# ECG.net
KiCad netlist of a schematic drawn in Altium Designer
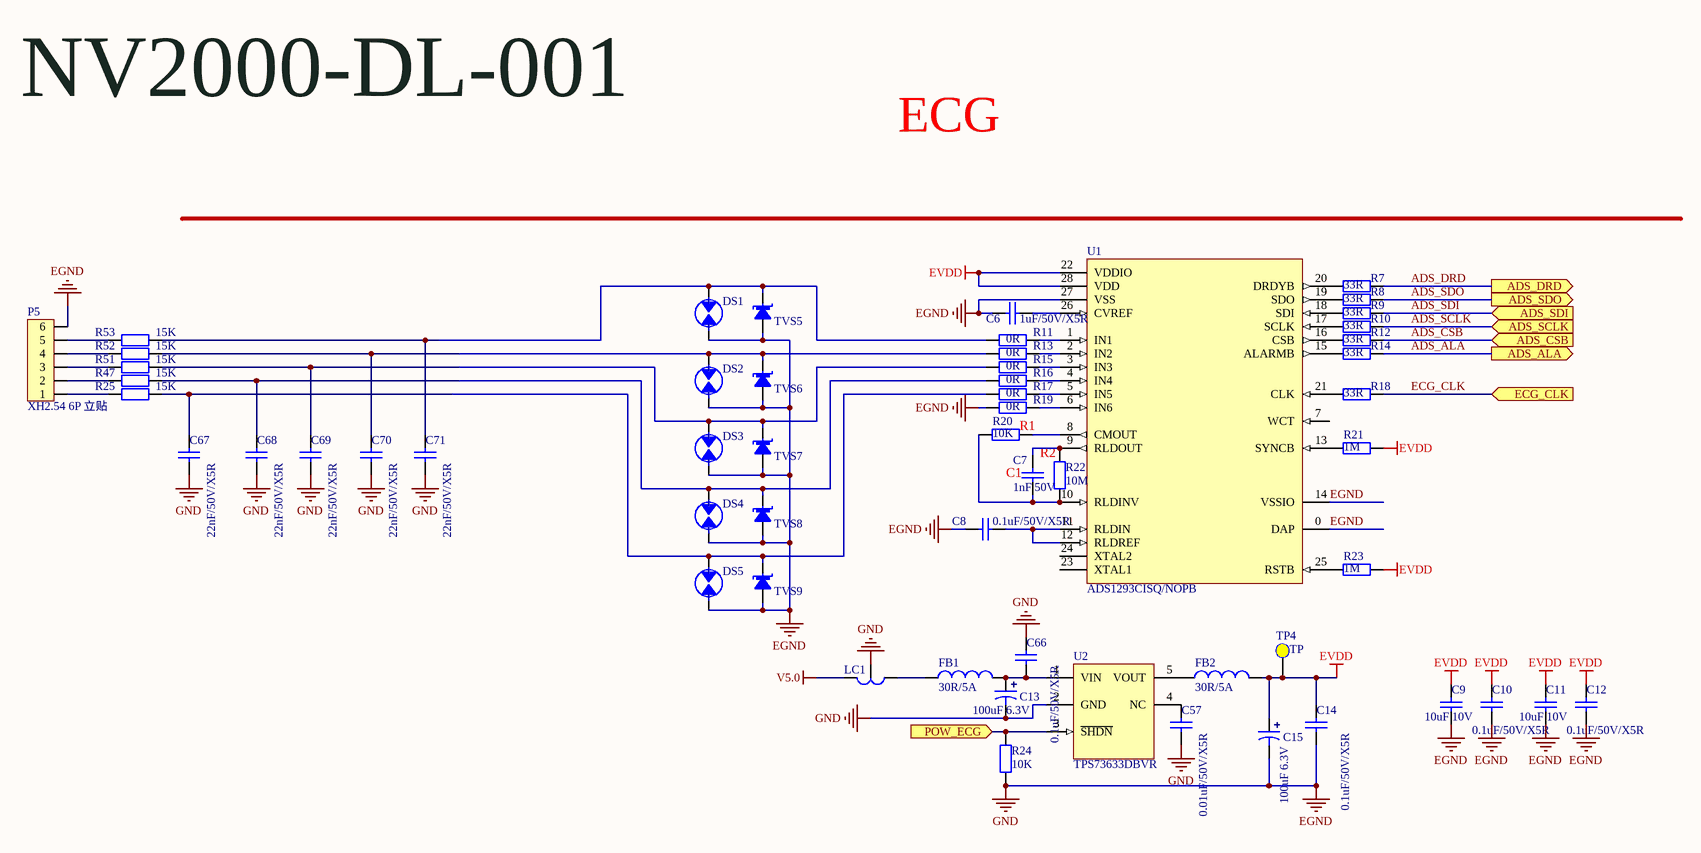
[diagram p0: ECG.SchDoc]

(export (version "E")
  (design (tool "Eeschema 10.0.6"))
  (components
    (comp (ref "C6")
      (value "1uF/50V/X5R")
      (footprint "SMD-0603C")
      (description "贴片电容 10%")
      (libsource (lib "XiaoyI") (part "CAP4"))
    )
    (comp (ref "C7")
      (value "1nF 50V")
      (footprint "SMD-0603C")
      (description "贴片电容 5%")
      (libsource (lib "XiaoyI") (part "CAP4"))
    )
    (comp (ref "C8")
      (value "0.1uF/50V/X5R")
      (footprint "SMD-0603C")
      (description "贴片电容 10%")
      (libsource (lib "XiaoyI") (part "CAP4"))
    )
    (comp (ref "C9")
      (value "10uF 10V")
      (footprint "SMD-0603C")
      (description "贴片电容 20%")
      (libsource (lib "XiaoyI") (part "CAP4"))
    )
    (comp (ref "C10")
      (value "0.1uF/50V/X5R")
      (footprint "SMD-0603C")
      (description "贴片电容 10%")
      (libsource (lib "XiaoyI") (part "CAP4"))
    )
    (comp (ref "C11")
      (value "10uF 10V")
      (footprint "SMD-0603C")
      (description "贴片电容 20%")
      (libsource (lib "XiaoyI") (part "CAP4"))
    )
    (comp (ref "C12")
      (value "0.1uF/50V/X5R")
      (footprint "SMD-0603C")
      (description "贴片电容 10%")
      (libsource (lib "XiaoyI") (part "CAP4"))
    )
    (comp (ref "C13")
      (value "100uF 6.3V")
      (footprint "SMD-3528-B")
      (description "钽电容")
      (libsource (lib "XiaoyI") (part "CAP2"))
    )
    (comp (ref "C14")
      (value "0.1uF/50V/X5R")
      (footprint "SMD-0603C")
      (description "贴片电容 10%")
      (libsource (lib "XiaoyI") (part "CAP4"))
    )
    (comp (ref "C15")
      (value "100uF 6.3V")
      (footprint "SMD-3528-B")
      (description "钽电容")
      (libsource (lib "XiaoyI") (part "CAP2"))
    )
    (comp (ref "C57")
      (value "0.01uF/50V/X5R")
      (footprint "SMD-0603C")
      (description "贴片电容 10%")
      (libsource (lib "XiaoyI") (part "CAP4"))
    )
    (comp (ref "C66")
      (value "0.1uF/50V/X5R")
      (footprint "SMD-0603C")
      (description "贴片电容 10%")
      (libsource (lib "XiaoyI") (part "CAP4"))
    )
    (comp (ref "C67")
      (value "22nF/50V/X5R")
      (footprint "SMD-0603C")
      (description "贴片电容 10%")
      (libsource (lib "XiaoyI") (part "CAP4"))
    )
    (comp (ref "C68")
      (value "22nF/50V/X5R")
      (footprint "SMD-0603C")
      (description "贴片电容 10%")
      (libsource (lib "XiaoyI") (part "CAP4"))
    )
    (comp (ref "C69")
      (value "22nF/50V/X5R")
      (footprint "SMD-0603C")
      (description "贴片电容 10%")
      (libsource (lib "XiaoyI") (part "CAP4"))
    )
    (comp (ref "C70")
      (value "22nF/50V/X5R")
      (footprint "SMD-0603C")
      (description "贴片电容 10%")
      (libsource (lib "XiaoyI") (part "CAP4"))
    )
    (comp (ref "C71")
      (value "22nF/50V/X5R")
      (footprint "SMD-0603C")
      (description "贴片电容 10%")
      (libsource (lib "XiaoyI") (part "CAP4"))
    )
    (comp (ref "DS1")
      (value "UN1812-90CSMD")
      (footprint "SMD-1812")
      (description "气体放电管 90V")
      (libsource (lib "ABB") (part "DISCHARE-1"))
    )
    (comp (ref "DS2")
      (value "UN1812-90CSMD")
      (footprint "SMD-1812")
      (description "气体放电管 90V")
      (libsource (lib "ABB") (part "DISCHARE-1"))
    )
    (comp (ref "DS3")
      (value "UN1812-90CSMD")
      (footprint "SMD-1812")
      (description "气体放电管 90V")
      (libsource (lib "ABB") (part "DISCHARE-1"))
    )
    (comp (ref "DS4")
      (value "UN1812-90CSMD")
      (footprint "SMD-1812")
      (description "气体放电管 90V")
      (libsource (lib "ABB") (part "DISCHARE-1"))
    )
    (comp (ref "DS5")
      (value "UN1812-90CSMD")
      (footprint "SMD-1812")
      (description "气体放电管 90V")
      (libsource (lib "ABB") (part "DISCHARE-1"))
    )
    (comp (ref "FB1")
      (value "30R/5A")
      (footprint "0603r")
      (description "Inductor")
      (fields (field (name "PUBLISHER") "Altium Limited"))
      (libsource (lib "Miscellaneous Devices") (part "Inductor"))
    )
    (comp (ref "FB2")
      (value "30R/5A")
      (footprint "0603r")
      (description "Inductor")
      (fields (field (name "PUBLISHER") "Altium Limited"))
      (libsource (lib "Miscellaneous Devices") (part "Inductor"))
    )
    (comp (ref "LC1")
      (value "NFM18PC104R1C3")
      (footprint "NFM21P-0805")
      (description "LC滤波器")
      (libsource (lib "XiaoyI") (part "SMD-EMIFIL-0603"))
    )
    (comp (ref "P5")
      (value "XH2.54 6P 立贴")
      (footprint "XH-2.54-6P-LI")
      (description "心电接口")
      (libsource (lib "ABB") (part "SIP-6"))
    )
    (comp (ref "R7")
      (value "33R")
      (footprint "SMD-0603")
      (description "贴片电阻 5%")
      (libsource (lib "ABB") (part "RES0"))
    )
    (comp (ref "R8")
      (value "33R")
      (footprint "SMD-0603")
      (description "贴片电阻 5%")
      (libsource (lib "ABB") (part "RES0"))
    )
    (comp (ref "R9")
      (value "33R")
      (footprint "SMD-0603")
      (description "贴片电阻 5%")
      (libsource (lib "ABB") (part "RES0"))
    )
    (comp (ref "R10")
      (value "33R")
      (footprint "SMD-0603")
      (description "贴片电阻 5%")
      (libsource (lib "ABB") (part "RES0"))
    )
    (comp (ref "R11")
      (value "0R")
      (footprint "SMD-0805")
      (description "贴片电阻 5%")
      (libsource (lib "") (part "RES0_2"))
    )
    (comp (ref "R12")
      (value "33R")
      (footprint "SMD-0603")
      (description "贴片电阻 5%")
      (libsource (lib "ABB") (part "RES0"))
    )
    (comp (ref "R13")
      (value "0R")
      (footprint "SMD-0805")
      (description "贴片电阻 5%")
      (libsource (lib "") (part "RES0_2"))
    )
    (comp (ref "R14")
      (value "33R")
      (footprint "SMD-0603")
      (description "贴片电阻 5%")
      (libsource (lib "ABB") (part "RES0"))
    )
    (comp (ref "R15")
      (value "0R")
      (footprint "SMD-0805")
      (description "贴片电阻 5%")
      (libsource (lib "") (part "RES0_2"))
    )
    (comp (ref "R16")
      (value "0R")
      (footprint "SMD-0805")
      (description "贴片电阻 5%")
      (libsource (lib "") (part "RES0_2"))
    )
    (comp (ref "R17")
      (value "0R")
      (footprint "SMD-0805")
      (description "贴片电阻 5%")
      (libsource (lib "") (part "RES0_2"))
    )
    (comp (ref "R18")
      (value "33R")
      (footprint "SMD-0603")
      (description "贴片电阻 5%")
      (libsource (lib "ABB") (part "RES0"))
    )
    (comp (ref "R19")
      (value "0R")
      (footprint "SMD-0805")
      (description "贴片电阻 5%")
      (libsource (lib "") (part "RES0_2"))
    )
    (comp (ref "R20")
      (value "10K")
      (footprint "SMD-0603")
      (description "贴片电阻 1%")
      (libsource (lib "ABB") (part "RES0"))
    )
    (comp (ref "R21")
      (value "1M")
      (footprint "SMD-0603")
      (description "贴片电阻 5%")
      (libsource (lib "ABB") (part "RES0"))
    )
    (comp (ref "R22")
      (value "10M")
      (footprint "SMD-0603")
      (description "贴片电阻 1%")
      (libsource (lib "") (part "RES0_1"))
    )
    (comp (ref "R23")
      (value "1M")
      (footprint "SMD-0603")
      (description "贴片电阻 5%")
      (libsource (lib "ABB") (part "RES0"))
    )
    (comp (ref "R24")
      (value "10K")
      (footprint "SMD-0603")
      (description "贴片电阻 1%")
      (libsource (lib "") (part "RES0_1"))
    )
    (comp (ref "R25")
      (value "15K")
      (footprint "SMD-0603")
      (description "贴片电阻 1%")
      (libsource (lib "") (part "RES0_2"))
    )
    (comp (ref "R47")
      (value "15K")
      (footprint "SMD-0603")
      (description "贴片电阻 1%")
      (libsource (lib "") (part "RES0_2"))
    )
    (comp (ref "R51")
      (value "15K")
      (footprint "SMD-0603")
      (description "贴片电阻 1%")
      (libsource (lib "") (part "RES0_2"))
    )
    (comp (ref "R52")
      (value "15K")
      (footprint "SMD-0603")
      (description "贴片电阻 1%")
      (libsource (lib "") (part "RES0_2"))
    )
    (comp (ref "R53")
      (value "15K")
      (footprint "SMD-0603")
      (description "贴片电阻 1%")
      (libsource (lib "") (part "RES0_2"))
    )
    (comp (ref "TP4") (value "TP") (footprint "TP") (libsource (lib "ABB") (part "TP_POINT")))
    (comp (ref "TVS5")
      (value "TVS-S")
      (footprint "SOD-323")
      (description "单向TVS")
      (libsource (lib "XiaoyI") (part "TVS-S"))
    )
    (comp (ref "TVS6")
      (value "TVS-S")
      (footprint "SOD-323")
      (description "单向TVS")
      (libsource (lib "XiaoyI") (part "TVS-S"))
    )
    (comp (ref "TVS7")
      (value "TVS-S")
      (footprint "SOD-323")
      (description "单向TVS")
      (libsource (lib "XiaoyI") (part "TVS-S"))
    )
    (comp (ref "TVS8")
      (value "TVS-S")
      (footprint "SOD-323")
      (description "单向TVS")
      (libsource (lib "XiaoyI") (part "TVS-S"))
    )
    (comp (ref "TVS9")
      (value "TVS-S")
      (footprint "SOD-323")
      (description "单向TVS")
      (libsource (lib "XiaoyI") (part "TVS-S"))
    )
    (comp (ref "U1")
      (value "ADS1293CISQ/NOPB")
      (footprint "QFN-28")
      (description "ECG AFE")
      (libsource (lib "ABB") (part "ADS1293"))
    )
    (comp (ref "U2")
      (value "TPS73633DBVR")
      (footprint "SOT23-5")
      (description "LDO")
      (libsource (lib "SYELE") (part "MCP1802"))
    )
  )
  (nets
    (net (code "1") (name "/ADS_ALA") (class "Default")
      (node (ref "R14") (pin "1") (pinfunction "1_1") (pintype "passive"))
    )
    (net (code "2") (name "/ADS_CSB") (class "Default")
      (node (ref "R12") (pin "1") (pinfunction "1_1") (pintype "passive"))
    )
    (net (code "3") (name "/ADS_DRD") (class "Default")
      (node (ref "R7") (pin "1") (pinfunction "1_1") (pintype "passive"))
    )
    (net (code "4") (name "/ADS_SCLK") (class "Default")
      (node (ref "R10") (pin "1") (pinfunction "1_1") (pintype "passive"))
    )
    (net (code "5") (name "/ADS_SDI") (class "Default")
      (node (ref "R9") (pin "1") (pinfunction "1_1") (pintype "passive"))
    )
    (net (code "6") (name "/ADS_SDO") (class "Default")
      (node (ref "R8") (pin "1") (pinfunction "1_1") (pintype "passive"))
    )
    (net (code "7") (name "/ECG_CLK") (class "Default")
      (node (ref "R18") (pin "1") (pinfunction "1_1") (pintype "passive"))
    )
    (net (code "8") (name "/POW_ECG") (class "Default")
      (node (ref "R24") (pin "1") (pinfunction "1_1") (pintype "passive"))
      (node (ref "U2") (pin "3") (pinfunction "~{SHDN}_3") (pintype "input"))
    )
    (net (code "9") (name "EGND") (class "Default")
      (node (ref "C10") (pin "1") (pinfunction "1_1") (pintype "passive"))
      (node (ref "C11") (pin "1") (pinfunction "1_1") (pintype "passive"))
      (node (ref "C12") (pin "1") (pinfunction "1_1") (pintype "passive"))
      (node (ref "C13") (pin "2") (pinfunction "2_2") (pintype "passive"))
      (node (ref "C14") (pin "1") (pinfunction "1_1") (pintype "passive"))
      (node (ref "C15") (pin "2") (pinfunction "2_2") (pintype "passive"))
      (node (ref "C57") (pin "1") (pinfunction "1_1") (pintype "passive"))
      (node (ref "C6") (pin "1") (pinfunction "1_1") (pintype "passive"))
      (node (ref "C66") (pin "2") (pinfunction "2_2") (pintype "passive"))
      (node (ref "C67") (pin "1") (pinfunction "1_1") (pintype "passive"))
      (node (ref "C68") (pin "1") (pinfunction "1_1") (pintype "passive"))
      (node (ref "C69") (pin "1") (pinfunction "1_1") (pintype "passive"))
      (node (ref "C70") (pin "1") (pinfunction "1_1") (pintype "passive"))
      (node (ref "C71") (pin "1") (pinfunction "1_1") (pintype "passive"))
      (node (ref "C8") (pin "1") (pinfunction "1_1") (pintype "passive"))
      (node (ref "C9") (pin "1") (pinfunction "1_1") (pintype "passive"))
      (node (ref "DS1") (pin "2") (pinfunction "2_2") (pintype "passive"))
      (node (ref "DS2") (pin "2") (pinfunction "2_2") (pintype "passive"))
      (node (ref "DS3") (pin "2") (pinfunction "2_2") (pintype "passive"))
      (node (ref "DS4") (pin "2") (pinfunction "2_2") (pintype "passive"))
      (node (ref "DS5") (pin "2") (pinfunction "2_2") (pintype "passive"))
      (node (ref "LC1") (pin "2") (pinfunction "2_2") (pintype "passive"))
      (node (ref "P5") (pin "6") (pinfunction "6_6") (pintype "passive"))
      (node (ref "R19") (pin "1") (pinfunction "1_1") (pintype "passive"))
      (node (ref "R24") (pin "2") (pinfunction "2_2") (pintype "passive"))
      (node (ref "TVS5") (pin "1") (pinfunction "A_1") (pintype "passive"))
      (node (ref "TVS6") (pin "1") (pinfunction "A_1") (pintype "passive"))
      (node (ref "TVS7") (pin "1") (pinfunction "A_1") (pintype "passive"))
      (node (ref "TVS8") (pin "1") (pinfunction "A_1") (pintype "passive"))
      (node (ref "TVS9") (pin "1") (pinfunction "A_1") (pintype "passive"))
      (node (ref "U1") (pin "0") (pinfunction "DAP_0") (pintype "power_in"))
      (node (ref "U1") (pin "14") (pinfunction "VSSIO_14") (pintype "power_in"))
      (node (ref "U1") (pin "27") (pinfunction "VSS_27") (pintype "power_in"))
      (node (ref "U2") (pin "2") (pinfunction "GND_2") (pintype "power_in"))
    )
    (net (code "10") (name "EVDD") (class "Default")
      (node (ref "C10") (pin "2") (pinfunction "2_2") (pintype "passive"))
      (node (ref "C11") (pin "2") (pinfunction "2_2") (pintype "passive"))
      (node (ref "C12") (pin "2") (pinfunction "2_2") (pintype "passive"))
      (node (ref "C14") (pin "2") (pinfunction "2_2") (pintype "passive"))
      (node (ref "C15") (pin "1") (pinfunction "1_1") (pintype "passive"))
      (node (ref "C9") (pin "2") (pinfunction "2_2") (pintype "passive"))
      (node (ref "FB2") (pin "2") (pinfunction "2_2") (pintype "passive"))
      (node (ref "R21") (pin "1") (pinfunction "1_1") (pintype "passive"))
      (node (ref "R23") (pin "1") (pinfunction "1_1") (pintype "passive"))
      (node (ref "TP4") (pin "1") (pinfunction "TP_1") (pintype "power_in"))
      (node (ref "U1") (pin "22") (pinfunction "VDDIO_22") (pintype "power_in"))
      (node (ref "U1") (pin "28") (pinfunction "VDD_28") (pintype "power_in"))
    )
    (net (code "11") (name "Net-(FB1-Pad1)") (class "Default")
      (node (ref "FB1") (pin "1") (pinfunction "1_1") (pintype "passive"))
      (node (ref "LC1") (pin "1") (pinfunction "1_1") (pintype "passive"))
    )
    (net (code "12") (name "Net-(P5-Pad1)") (class "Default")
      (node (ref "P5") (pin "1") (pinfunction "1_1") (pintype "passive"))
      (node (ref "R25") (pin "1") (pinfunction "1_1") (pintype "passive"))
    )
    (net (code "13") (name "Net-(P5-Pad2)") (class "Default")
      (node (ref "P5") (pin "2") (pinfunction "2_2") (pintype "passive"))
      (node (ref "R47") (pin "1") (pinfunction "1_1") (pintype "passive"))
    )
    (net (code "14") (name "Net-(P5-Pad3)") (class "Default")
      (node (ref "P5") (pin "3") (pinfunction "3_3") (pintype "passive"))
      (node (ref "R51") (pin "1") (pinfunction "1_1") (pintype "passive"))
    )
    (net (code "15") (name "Net-(P5-Pad4)") (class "Default")
      (node (ref "P5") (pin "4") (pinfunction "4_4") (pintype "passive"))
      (node (ref "R52") (pin "1") (pinfunction "1_1") (pintype "passive"))
    )
    (net (code "16") (name "Net-(P5-Pad5)") (class "Default")
      (node (ref "P5") (pin "5") (pinfunction "5_5") (pintype "passive"))
      (node (ref "R53") (pin "1") (pinfunction "1_1") (pintype "passive"))
    )
    (net (code "17") (name "Net-(TVS5-B)") (class "Default")
      (node (ref "C71") (pin "2") (pinfunction "2_2") (pintype "passive"))
      (node (ref "DS1") (pin "1") (pinfunction "1_1") (pintype "passive"))
      (node (ref "R11") (pin "1") (pinfunction "1_1") (pintype "passive"))
      (node (ref "R53") (pin "2") (pinfunction "2_2") (pintype "passive"))
      (node (ref "TVS5") (pin "2") (pinfunction "B_2") (pintype "passive"))
    )
    (net (code "18") (name "Net-(TVS6-B)") (class "Default")
      (node (ref "C70") (pin "2") (pinfunction "2_2") (pintype "passive"))
      (node (ref "DS2") (pin "1") (pinfunction "1_1") (pintype "passive"))
      (node (ref "R13") (pin "1") (pinfunction "1_1") (pintype "passive"))
      (node (ref "R52") (pin "2") (pinfunction "2_2") (pintype "passive"))
      (node (ref "TVS6") (pin "2") (pinfunction "B_2") (pintype "passive"))
    )
    (net (code "19") (name "Net-(TVS7-B)") (class "Default")
      (node (ref "C69") (pin "2") (pinfunction "2_2") (pintype "passive"))
      (node (ref "DS3") (pin "1") (pinfunction "1_1") (pintype "passive"))
      (node (ref "R15") (pin "1") (pinfunction "1_1") (pintype "passive"))
      (node (ref "R51") (pin "2") (pinfunction "2_2") (pintype "passive"))
      (node (ref "TVS7") (pin "2") (pinfunction "B_2") (pintype "passive"))
    )
    (net (code "20") (name "Net-(TVS8-B)") (class "Default")
      (node (ref "C68") (pin "2") (pinfunction "2_2") (pintype "passive"))
      (node (ref "DS4") (pin "1") (pinfunction "1_1") (pintype "passive"))
      (node (ref "R16") (pin "1") (pinfunction "1_1") (pintype "passive"))
      (node (ref "R47") (pin "2") (pinfunction "2_2") (pintype "passive"))
      (node (ref "TVS8") (pin "2") (pinfunction "B_2") (pintype "passive"))
    )
    (net (code "21") (name "Net-(TVS9-B)") (class "Default")
      (node (ref "C67") (pin "2") (pinfunction "2_2") (pintype "passive"))
      (node (ref "DS5") (pin "1") (pinfunction "1_1") (pintype "passive"))
      (node (ref "R17") (pin "1") (pinfunction "1_1") (pintype "passive"))
      (node (ref "R25") (pin "2") (pinfunction "2_2") (pintype "passive"))
      (node (ref "TVS9") (pin "2") (pinfunction "B_2") (pintype "passive"))
    )
    (net (code "22") (name "Net-(U1-ALARMB)") (class "Default")
      (node (ref "R14") (pin "2") (pinfunction "2_2") (pintype "passive"))
      (node (ref "U1") (pin "15") (pinfunction "ALARMB_15") (pintype "output"))
    )
    (net (code "23") (name "Net-(U1-CLK)") (class "Default")
      (node (ref "R18") (pin "2") (pinfunction "2_2") (pintype "passive"))
      (node (ref "U1") (pin "21") (pinfunction "CLK_21") (pintype "input"))
    )
    (net (code "24") (name "Net-(U1-CMOUT)") (class "Default")
      (node (ref "R20") (pin "1") (pinfunction "1_1") (pintype "passive"))
      (node (ref "U1") (pin "8") (pinfunction "CMOUT_8") (pintype "output"))
    )
    (net (code "25") (name "Net-(U1-CSB)") (class "Default")
      (node (ref "R12") (pin "2") (pinfunction "2_2") (pintype "passive"))
      (node (ref "U1") (pin "16") (pinfunction "CSB_16") (pintype "output"))
    )
    (net (code "26") (name "Net-(U1-CVREF)") (class "Default")
      (node (ref "C6") (pin "2") (pinfunction "2_2") (pintype "passive"))
      (node (ref "U1") (pin "26") (pinfunction "CVREF_26") (pintype "input"))
    )
    (net (code "27") (name "Net-(U1-DRDYB)") (class "Default")
      (node (ref "R7") (pin "2") (pinfunction "2_2") (pintype "passive"))
      (node (ref "U1") (pin "20") (pinfunction "DRDYB_20") (pintype "output"))
    )
    (net (code "28") (name "Net-(U1-IN1)") (class "Default")
      (node (ref "R11") (pin "2") (pinfunction "2_2") (pintype "passive"))
      (node (ref "U1") (pin "1") (pinfunction "IN1_1") (pintype "input"))
    )
    (net (code "29") (name "Net-(U1-IN2)") (class "Default")
      (node (ref "R13") (pin "2") (pinfunction "2_2") (pintype "passive"))
      (node (ref "U1") (pin "2") (pinfunction "IN2_2") (pintype "input"))
    )
    (net (code "30") (name "Net-(U1-IN3)") (class "Default")
      (node (ref "R15") (pin "2") (pinfunction "2_2") (pintype "passive"))
      (node (ref "U1") (pin "3") (pinfunction "IN3_3") (pintype "input"))
    )
    (net (code "31") (name "Net-(U1-IN4)") (class "Default")
      (node (ref "R16") (pin "2") (pinfunction "2_2") (pintype "passive"))
      (node (ref "U1") (pin "4") (pinfunction "IN4_4") (pintype "input"))
    )
    (net (code "32") (name "Net-(U1-IN5)") (class "Default")
      (node (ref "R17") (pin "2") (pinfunction "2_2") (pintype "passive"))
      (node (ref "U1") (pin "5") (pinfunction "IN5_5") (pintype "input"))
    )
    (net (code "33") (name "Net-(U1-IN6)") (class "Default")
      (node (ref "R19") (pin "2") (pinfunction "2_2") (pintype "passive"))
      (node (ref "U1") (pin "6") (pinfunction "IN6_6") (pintype "input"))
    )
    (net (code "34") (name "Net-(U1-RLDIN)") (class "Default")
      (node (ref "C8") (pin "2") (pinfunction "2_2") (pintype "passive"))
      (node (ref "U1") (pin "11") (pinfunction "RLDIN_11") (pintype "input"))
      (node (ref "U1") (pin "12") (pinfunction "RLDREF_12") (pintype "input"))
    )
    (net (code "35") (name "Net-(U1-RLDINV)") (class "Default")
      (node (ref "C7") (pin "2") (pinfunction "2_2") (pintype "passive"))
      (node (ref "R20") (pin "2") (pinfunction "2_2") (pintype "passive"))
      (node (ref "R22") (pin "2") (pinfunction "2_2") (pintype "passive"))
      (node (ref "U1") (pin "10") (pinfunction "RLDINV_10") (pintype "input"))
    )
    (net (code "36") (name "Net-(U1-RLDOUT)") (class "Default")
      (node (ref "C7") (pin "1") (pinfunction "1_1") (pintype "passive"))
      (node (ref "R22") (pin "1") (pinfunction "1_1") (pintype "passive"))
      (node (ref "U1") (pin "9") (pinfunction "RLDOUT_9") (pintype "output"))
    )
    (net (code "37") (name "Net-(U1-RSTB)") (class "Default")
      (node (ref "R23") (pin "2") (pinfunction "2_2") (pintype "passive"))
      (node (ref "U1") (pin "25") (pinfunction "RSTB_25") (pintype "input"))
    )
    (net (code "38") (name "Net-(U1-SCLK)") (class "Default")
      (node (ref "R10") (pin "2") (pinfunction "2_2") (pintype "passive"))
      (node (ref "U1") (pin "17") (pinfunction "SCLK_17") (pintype "input"))
    )
    (net (code "39") (name "Net-(U1-SDI)") (class "Default")
      (node (ref "R9") (pin "2") (pinfunction "2_2") (pintype "passive"))
      (node (ref "U1") (pin "18") (pinfunction "SDI_18") (pintype "input"))
    )
    (net (code "40") (name "Net-(U1-SDO)") (class "Default")
      (node (ref "R8") (pin "2") (pinfunction "2_2") (pintype "passive"))
      (node (ref "U1") (pin "19") (pinfunction "SDO_19") (pintype "output"))
    )
    (net (code "41") (name "Net-(U1-SYNCB)") (class "Default")
      (node (ref "R21") (pin "2") (pinfunction "2_2") (pintype "passive"))
      (node (ref "U1") (pin "13") (pinfunction "SYNCB_13") (pintype "input"))
    )
    (net (code "42") (name "Net-(U2-NC)") (class "Default")
      (node (ref "C57") (pin "2") (pinfunction "2_2") (pintype "passive"))
      (node (ref "U2") (pin "4") (pinfunction "NC_4") (pintype "passive"))
    )
    (net (code "43") (name "Net-(U2-VIN)") (class "Default")
      (node (ref "C13") (pin "1") (pinfunction "1_1") (pintype "passive"))
      (node (ref "C66") (pin "1") (pinfunction "1_1") (pintype "passive"))
      (node (ref "FB1") (pin "2") (pinfunction "2_2") (pintype "passive"))
      (node (ref "U2") (pin "1") (pinfunction "VIN_1") (pintype "power_in"))
    )
    (net (code "44") (name "Net-(U2-VOUT)") (class "Default")
      (node (ref "FB2") (pin "1") (pinfunction "1_1") (pintype "passive"))
      (node (ref "U2") (pin "5") (pinfunction "VOUT_5") (pintype "power_in"))
    )
    (net (code "45") (name "V5.0") (class "Default")
      (node (ref "LC1") (pin "3") (pinfunction "3_3") (pintype "passive"))
    )
    (net (code "46") (name "unconnected-(U1-WCT-Pad7)") (class "Default")
      (node (ref "U1") (pin "7") (pinfunction "WCT_7") (pintype "input"))
    )
    (net (code "47") (name "unconnected-(U1-XTAL1-Pad23)") (class "Default")
      (node (ref "U1") (pin "23") (pinfunction "XTAL1_23") (pintype "tri_state"))
    )
    (net (code "48") (name "unconnected-(U1-XTAL2-Pad24)") (class "Default")
      (node (ref "U1") (pin "24") (pinfunction "XTAL2_24") (pintype "tri_state"))
    )
  )
)
